# FuseReset_0_1.net
KiCad netlist of a schematic drawn in EAGLE
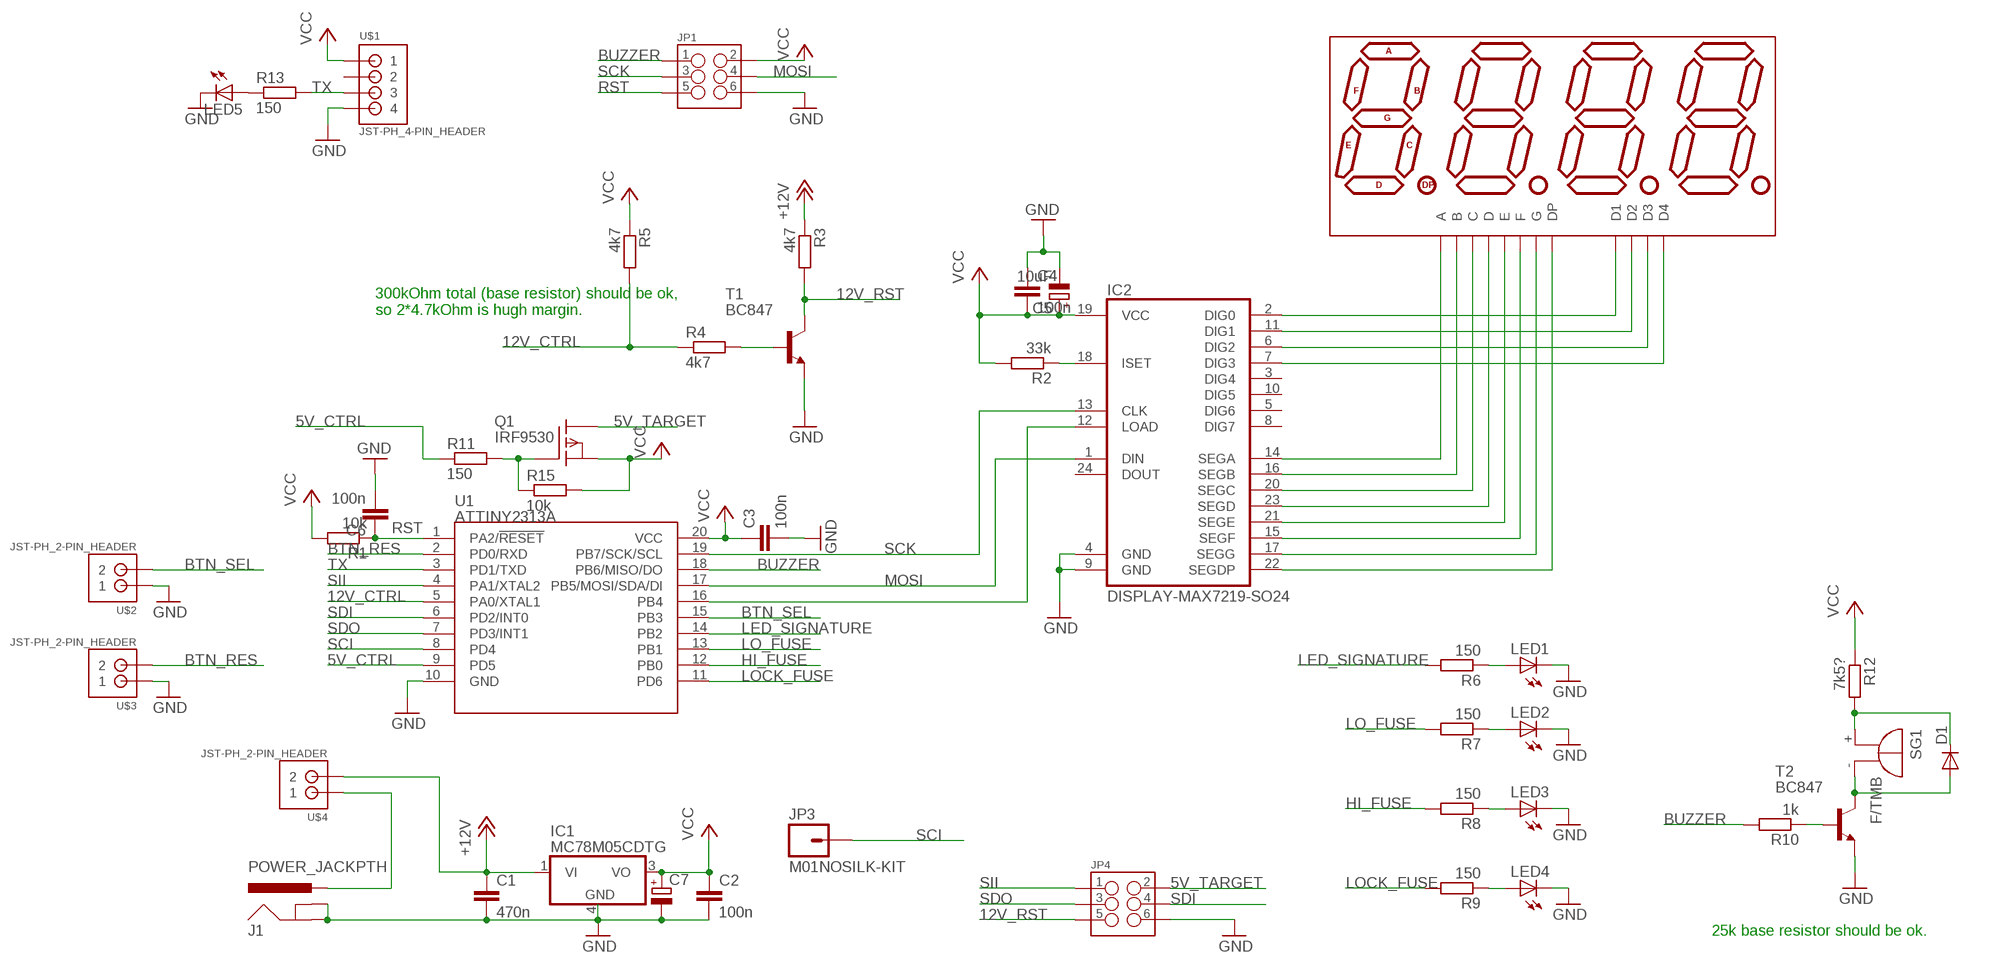
[diagram p0: schematic, sheet 1]

(export (version "E")
  (design (tool "Eeschema 10.0.6"))
  (components
    (comp (ref "C1")
      (value "470n")
      (footprint "eagle-import:C0805")
      (libsource (lib "eagle-import") (part "C-EUC0805"))
    )
    (comp (ref "C2")
      (value "100n")
      (footprint "eagle-import:C0805")
      (libsource (lib "eagle-import") (part "C-EUC0805"))
    )
    (comp (ref "C3")
      (value "100n")
      (footprint "eagle-import:C0805")
      (libsource (lib "eagle-import") (part "C-EUC0805"))
    )
    (comp (ref "C4")
      (value "100n")
      (footprint "eagle-import:C0805")
      (libsource (lib "eagle-import") (part "C-EUC0805"))
    )
    (comp (ref "C5")
      (value "10uF")
      (footprint "eagle-import:153CLV-0405")
      (libsource (lib "eagle-import") (part "resistor_CPOL-EU153CLV-0405"))
    )
    (comp (ref "C6")
      (value "100n")
      (footprint "eagle-import:C0805")
      (libsource (lib "eagle-import") (part "C-EUC0805"))
    )
    (comp (ref "C7")
      (value "CPOL-EUE2-5")
      (footprint "eagle-import:E2-5")
      (libsource (lib "eagle-import") (part "CPOL-EUE2-5"))
    )
    (comp (ref "D1")
      (value "DIODE-DO-214AC")
      (footprint "eagle-import:DO-214AC")
      (libsource (lib "eagle-import") (part "DIODE-DO-214AC"))
    )
    (comp (ref "DISP2")
      (value "7-SEGMENT-4DIGIT-COUNTER")
      (footprint "eagle-import:7-SEGMENT-4DIGIT-COUNTER-0.36_")
      (libsource (lib "eagle-import") (part "7-SEGMENT-4DIGIT-COUNTER"))
    )
    (comp (ref "IC1")
      (value "MC78M05CDTG")
      (footprint "eagle-import:DPACK_3")
      (libsource (lib "eagle-import") (part "MC78M05CDTG"))
    )
    (comp (ref "IC2")
      (value "DISPLAY-MAX7219-SO24")
      (footprint "eagle-import:SO24L")
      (libsource (lib "eagle-import") (part "DISPLAY-MAX7219-SO24"))
    )
    (comp (ref "J1")
      (value "POWER_JACKPTH")
      (footprint "eagle-import:POWER_JACK_PTH")
      (libsource (lib "eagle-import") (part "POWER_JACKPTH"))
    )
    (comp (ref "JP1")
      (value "M03X2SHROUD")
      (footprint "eagle-import:2X3-SHROUDED")
      (libsource (lib "eagle-import") (part "M03X2SHROUD"))
    )
    (comp (ref "JP3")
      (value "M01NOSILK-KIT")
      (footprint "eagle-import:1X01NS-KIT")
      (libsource (lib "eagle-import") (part "M01NOSILK-KIT"))
    )
    (comp (ref "JP4")
      (value "M03X2SHROUD")
      (footprint "eagle-import:2X3-SHROUDED")
      (libsource (lib "eagle-import") (part "M03X2SHROUD"))
    )
    (comp (ref "LED1")
      (value "LED3MM")
      (footprint "eagle-import:LED3MM")
      (libsource (lib "eagle-import") (part "LED3MM"))
    )
    (comp (ref "LED2")
      (value "LED3MM")
      (footprint "eagle-import:LED3MM")
      (libsource (lib "eagle-import") (part "LED3MM"))
    )
    (comp (ref "LED3")
      (value "LED3MM")
      (footprint "eagle-import:LED3MM")
      (libsource (lib "eagle-import") (part "LED3MM"))
    )
    (comp (ref "LED4")
      (value "LED3MM")
      (footprint "eagle-import:LED3MM")
      (libsource (lib "eagle-import") (part "LED3MM"))
    )
    (comp (ref "LED5")
      (value "LED-0805")
      (footprint "eagle-import:LED-805")
      (libsource (lib "eagle-import") (part "LED-0805"))
    )
    (comp (ref "Q1")
      (value "IRF9530")
      (footprint "eagle-import:TO220")
      (libsource (lib "eagle-import") (part "IRF9530"))
    )
    (comp (ref "R1")
      (value "10k")
      (footprint "eagle-import:R0805")
      (libsource (lib "eagle-import") (part "R-EU_R0805"))
    )
    (comp (ref "R2")
      (value "33k")
      (footprint "eagle-import:R0805")
      (libsource (lib "eagle-import") (part "R-EU_R0805"))
    )
    (comp (ref "R3")
      (value "4k7")
      (footprint "eagle-import:R0805")
      (libsource (lib "eagle-import") (part "R-EU_R0805"))
    )
    (comp (ref "R4")
      (value "4k7")
      (footprint "eagle-import:R0805")
      (libsource (lib "eagle-import") (part "R-EU_R0805"))
    )
    (comp (ref "R5")
      (value "4k7")
      (footprint "eagle-import:R0805")
      (libsource (lib "eagle-import") (part "R-EU_R0805"))
    )
    (comp (ref "R6")
      (value "150")
      (footprint "eagle-import:R0805")
      (libsource (lib "eagle-import") (part "R-EU_R0805"))
    )
    (comp (ref "R7")
      (value "150")
      (footprint "eagle-import:R0805")
      (libsource (lib "eagle-import") (part "R-EU_R0805"))
    )
    (comp (ref "R8")
      (value "150")
      (footprint "eagle-import:R0805")
      (libsource (lib "eagle-import") (part "R-EU_R0805"))
    )
    (comp (ref "R9")
      (value "150")
      (footprint "eagle-import:R0805")
      (libsource (lib "eagle-import") (part "R-EU_R0805"))
    )
    (comp (ref "R10")
      (value "1k")
      (footprint "eagle-import:R0805")
      (libsource (lib "eagle-import") (part "R-EU_R0805"))
    )
    (comp (ref "R11")
      (value "150")
      (footprint "eagle-import:R0805")
      (libsource (lib "eagle-import") (part "R-EU_R0805"))
    )
    (comp (ref "R12")
      (value "7k5?")
      (footprint "eagle-import:R0805")
      (libsource (lib "eagle-import") (part "R-EU_R0805"))
    )
    (comp (ref "R13")
      (value "150")
      (footprint "eagle-import:R0805")
      (libsource (lib "eagle-import") (part "R-EU_R0805"))
    )
    (comp (ref "R15")
      (value "10k")
      (footprint "eagle-import:R0805")
      (libsource (lib "eagle-import") (part "R-EU_R0805"))
    )
    (comp (ref "SG1")
      (value "F/TMB")
      (footprint "eagle-import:F_TMB")
      (libsource (lib "eagle-import") (part "F/TMB"))
    )
    (comp (ref "T1")
      (value "BC847")
      (footprint "eagle-import:SOT23")
      (libsource (lib "eagle-import") (part "BC847"))
    )
    (comp (ref "T2")
      (value "BC847")
      (footprint "eagle-import:SOT23")
      (libsource (lib "eagle-import") (part "BC847"))
    )
    (comp (ref "U$1")
      (value "JST-PH_4-PIN_HEADER")
      (footprint "eagle-import:JST_B4B-PH_HEADER")
      (libsource (lib "eagle-import") (part "JST-PH_4-PIN_HEADER"))
    )
    (comp (ref "U$2")
      (value "JST-PH_2-PIN_HEADER")
      (footprint "eagle-import:JST_B2B-PH_HEADER")
      (libsource (lib "eagle-import") (part "JST-PH_2-PIN_HEADER"))
    )
    (comp (ref "U$3")
      (value "JST-PH_2-PIN_HEADER")
      (footprint "eagle-import:JST_B2B-PH_HEADER")
      (libsource (lib "eagle-import") (part "JST-PH_2-PIN_HEADER"))
    )
    (comp (ref "U$4")
      (value "JST-PH_2-PIN_HEADER")
      (footprint "eagle-import:JST_B2B-PH_HEADER")
      (libsource (lib "eagle-import") (part "JST-PH_2-PIN_HEADER"))
    )
    (comp (ref "U1")
      (value "ATTINY2313A")
      (footprint "eagle-import:SOP20W")
      (libsource (lib "eagle-import") (part "ATTINY2313A"))
    )
  )
  (nets
    (net (code "1") (name "+12V") (class "Default")
      (node (ref "C1") (pin "1") (pinfunction "1_1") (pintype "passive"))
      (node (ref "IC1") (pin "1") (pinfunction "VI_1") (pintype "input"))
      (node (ref "R3") (pin "1") (pinfunction "1_1") (pintype "passive"))
      (node (ref "U$4") (pin "P2") (pinfunction "2_P2") (pintype "bidirectional"))
    )
    (net (code "2") (name "/5V_CTRL") (class "Default")
      (node (ref "R11") (pin "1") (pinfunction "1_1") (pintype "passive"))
      (node (ref "U1") (pin "9") (pinfunction "PD5_9") (pintype "bidirectional"))
    )
    (net (code "3") (name "/5V_TARGET") (class "Default")
      (node (ref "JP4") (pin "2") (pinfunction "2_2") (pintype "bidirectional"))
      (node (ref "Q1") (pin "2") (pinfunction "D_2") (pintype "passive"))
    )
    (net (code "4") (name "/12V_CTRL") (class "Default")
      (node (ref "R4") (pin "1") (pinfunction "1_1") (pintype "passive"))
      (node (ref "R5") (pin "2") (pinfunction "2_2") (pintype "passive"))
      (node (ref "U1") (pin "5") (pinfunction "PA0/XTAL1_5") (pintype "bidirectional"))
    )
    (net (code "5") (name "/12V_RST") (class "Default")
      (node (ref "JP4") (pin "5") (pinfunction "5_5") (pintype "bidirectional"))
      (node (ref "R3") (pin "2") (pinfunction "2_2") (pintype "passive"))
      (node (ref "T1") (pin "3") (pinfunction "C_3") (pintype "passive"))
    )
    (net (code "6") (name "/BTN_RES") (class "Default")
      (node (ref "U$3") (pin "P2") (pinfunction "2_P2") (pintype "bidirectional"))
      (node (ref "U1") (pin "2") (pinfunction "PD0/RXD_2") (pintype "bidirectional"))
    )
    (net (code "7") (name "/BTN_SEL") (class "Default")
      (node (ref "U$2") (pin "P2") (pinfunction "2_P2") (pintype "bidirectional"))
      (node (ref "U1") (pin "15") (pinfunction "PB3_15") (pintype "bidirectional"))
    )
    (net (code "8") (name "/BUZZER") (class "Default")
      (node (ref "JP1") (pin "1") (pinfunction "1_1") (pintype "bidirectional"))
      (node (ref "R10") (pin "2") (pinfunction "2_2") (pintype "passive"))
      (node (ref "U1") (pin "18") (pinfunction "PB6/MISO/DO_18") (pintype "bidirectional"))
    )
    (net (code "9") (name "/HI_FUSE") (class "Default")
      (node (ref "R8") (pin "2") (pinfunction "2_2") (pintype "passive"))
      (node (ref "U1") (pin "12") (pinfunction "PB0_12") (pintype "bidirectional"))
    )
    (net (code "10") (name "/LED_SIGNATURE") (class "Default")
      (node (ref "R6") (pin "2") (pinfunction "2_2") (pintype "passive"))
      (node (ref "U1") (pin "14") (pinfunction "PB2_14") (pintype "bidirectional"))
    )
    (net (code "11") (name "/LOCK_FUSE") (class "Default")
      (node (ref "R9") (pin "2") (pinfunction "2_2") (pintype "passive"))
      (node (ref "U1") (pin "11") (pinfunction "PD6_11") (pintype "bidirectional"))
    )
    (net (code "12") (name "/LO_FUSE") (class "Default")
      (node (ref "R7") (pin "2") (pinfunction "2_2") (pintype "passive"))
      (node (ref "U1") (pin "13") (pinfunction "PB1_13") (pintype "bidirectional"))
    )
    (net (code "13") (name "/MOSI") (class "Default")
      (node (ref "IC2") (pin "1") (pinfunction "DIN_1") (pintype "input"))
      (node (ref "JP1") (pin "4") (pinfunction "4_4") (pintype "bidirectional"))
      (node (ref "U1") (pin "17") (pinfunction "PB5/MOSI/SDA/DI_17") (pintype "bidirectional"))
    )
    (net (code "14") (name "/RST") (class "Default")
      (node (ref "C6") (pin "1") (pinfunction "1_1") (pintype "passive"))
      (node (ref "JP1") (pin "5") (pinfunction "5_5") (pintype "bidirectional"))
      (node (ref "R1") (pin "1") (pinfunction "1_1") (pintype "passive"))
      (node (ref "U1") (pin "1") (pinfunction "PA2/~{RESET}_1") (pintype "bidirectional"))
    )
    (net (code "15") (name "/SCI") (class "Default")
      (node (ref "JP3") (pin "1") (pinfunction "1_1") (pintype "passive"))
      (node (ref "U1") (pin "8") (pinfunction "PD4_8") (pintype "bidirectional"))
    )
    (net (code "16") (name "/SCK") (class "Default")
      (node (ref "IC2") (pin "13") (pinfunction "CLK_13") (pintype "input"))
      (node (ref "JP1") (pin "3") (pinfunction "3_3") (pintype "bidirectional"))
      (node (ref "U1") (pin "19") (pinfunction "PB7/SCK/SCL_19") (pintype "bidirectional"))
    )
    (net (code "17") (name "/SDI") (class "Default")
      (node (ref "JP4") (pin "4") (pinfunction "4_4") (pintype "bidirectional"))
      (node (ref "U1") (pin "6") (pinfunction "PD2/INT0_6") (pintype "bidirectional"))
    )
    (net (code "18") (name "/SDO") (class "Default")
      (node (ref "JP4") (pin "3") (pinfunction "3_3") (pintype "bidirectional"))
      (node (ref "U1") (pin "7") (pinfunction "PD3/INT1_7") (pintype "bidirectional"))
    )
    (net (code "19") (name "/SII") (class "Default")
      (node (ref "JP4") (pin "1") (pinfunction "1_1") (pintype "bidirectional"))
      (node (ref "U1") (pin "4") (pinfunction "PA1/XTAL2_4") (pintype "bidirectional"))
    )
    (net (code "20") (name "/TX") (class "Default")
      (node (ref "R13") (pin "2") (pinfunction "2_2") (pintype "passive"))
      (node (ref "U$1") (pin "P3") (pinfunction "3_P3") (pintype "bidirectional"))
      (node (ref "U1") (pin "3") (pinfunction "PD1/TXD_3") (pintype "bidirectional"))
    )
    (net (code "21") (name "GND") (class "Default")
      (node (ref "C1") (pin "2") (pinfunction "2_2") (pintype "passive"))
      (node (ref "C2") (pin "2") (pinfunction "2_2") (pintype "passive"))
      (node (ref "C3") (pin "2") (pinfunction "2_2") (pintype "passive"))
      (node (ref "C4") (pin "1") (pinfunction "1_1") (pintype "passive"))
      (node (ref "C5") (pin "-") (pinfunction "-_-") (pintype "passive"))
      (node (ref "C6") (pin "2") (pinfunction "2_2") (pintype "passive"))
      (node (ref "C7") (pin "-") (pinfunction "-_-") (pintype "passive"))
      (node (ref "IC1") (pin "4") (pinfunction "GND_4") (pintype "passive"))
      (node (ref "IC2") (pin "4") (pinfunction "GND_4") (pintype "power_in"))
      (node (ref "IC2") (pin "9") (pinfunction "GND_9") (pintype "power_in"))
      (node (ref "J1") (pin "GND") (pinfunction "GND_GND") (pintype "bidirectional"))
      (node (ref "J1") (pin "GNDBREAK") (pinfunction "GNDBREAK_GNDBREAK") (pintype "bidirectional"))
      (node (ref "JP1") (pin "6") (pinfunction "6_6") (pintype "bidirectional"))
      (node (ref "JP4") (pin "6") (pinfunction "6_6") (pintype "bidirectional"))
      (node (ref "LED1") (pin "K") (pinfunction "C_K") (pintype "passive"))
      (node (ref "LED2") (pin "K") (pinfunction "C_K") (pintype "passive"))
      (node (ref "LED3") (pin "K") (pinfunction "C_K") (pintype "passive"))
      (node (ref "LED4") (pin "K") (pinfunction "C_K") (pintype "passive"))
      (node (ref "LED5") (pin "C") (pinfunction "C_C") (pintype "passive"))
      (node (ref "T1") (pin "2") (pinfunction "E_2") (pintype "passive"))
      (node (ref "T2") (pin "2") (pinfunction "E_2") (pintype "passive"))
      (node (ref "U$1") (pin "P4") (pinfunction "4_P4") (pintype "bidirectional"))
      (node (ref "U$2") (pin "P1") (pinfunction "1_P1") (pintype "bidirectional"))
      (node (ref "U$3") (pin "P1") (pinfunction "1_P1") (pintype "bidirectional"))
      (node (ref "U1") (pin "10") (pinfunction "GND_10") (pintype "bidirectional"))
    )
    (net (code "22") (name "Net-(D1-A)") (class "Default")
      (node (ref "D1") (pin "2") (pinfunction "A_2") (pintype "passive"))
      (node (ref "SG1") (pin "-") (pinfunction "-_-") (pintype "passive"))
      (node (ref "T2") (pin "3") (pinfunction "C_3") (pintype "passive"))
    )
    (net (code "23") (name "Net-(D1-C)") (class "Default")
      (node (ref "D1") (pin "1") (pinfunction "C_1") (pintype "passive"))
      (node (ref "R12") (pin "2") (pinfunction "2_2") (pintype "passive"))
      (node (ref "SG1") (pin "+") (pinfunction "+_+") (pintype "passive"))
    )
    (net (code "24") (name "Net-(DISP2-A)") (class "Default")
      (node (ref "DISP2") (pin "11") (pinfunction "A_11") (pintype "bidirectional"))
      (node (ref "IC2") (pin "14") (pinfunction "SEGA_14") (pintype "output"))
    )
    (net (code "25") (name "Net-(DISP2-B)") (class "Default")
      (node (ref "DISP2") (pin "7") (pinfunction "B_7") (pintype "bidirectional"))
      (node (ref "IC2") (pin "16") (pinfunction "SEGB_16") (pintype "output"))
    )
    (net (code "26") (name "Net-(DISP2-C)") (class "Default")
      (node (ref "DISP2") (pin "4") (pinfunction "C_4") (pintype "bidirectional"))
      (node (ref "IC2") (pin "20") (pinfunction "SEGC_20") (pintype "output"))
    )
    (net (code "27") (name "Net-(DISP2-D)") (class "Default")
      (node (ref "DISP2") (pin "2") (pinfunction "D_2") (pintype "bidirectional"))
      (node (ref "IC2") (pin "23") (pinfunction "SEGD_23") (pintype "output"))
    )
    (net (code "28") (name "Net-(DISP2-D1)") (class "Default")
      (node (ref "DISP2") (pin "12") (pinfunction "D1_12") (pintype "bidirectional"))
      (node (ref "IC2") (pin "2") (pinfunction "DIG0_2") (pintype "output"))
    )
    (net (code "29") (name "Net-(DISP2-D2)") (class "Default")
      (node (ref "DISP2") (pin "9") (pinfunction "D2_9") (pintype "bidirectional"))
      (node (ref "IC2") (pin "11") (pinfunction "DIG1_11") (pintype "output"))
    )
    (net (code "30") (name "Net-(DISP2-D3)") (class "Default")
      (node (ref "DISP2") (pin "8") (pinfunction "D3_8") (pintype "bidirectional"))
      (node (ref "IC2") (pin "6") (pinfunction "DIG2_6") (pintype "output"))
    )
    (net (code "31") (name "Net-(DISP2-D4)") (class "Default")
      (node (ref "DISP2") (pin "6") (pinfunction "D4_6") (pintype "bidirectional"))
      (node (ref "IC2") (pin "7") (pinfunction "DIG3_7") (pintype "output"))
    )
    (net (code "32") (name "Net-(DISP2-DP)") (class "Default")
      (node (ref "DISP2") (pin "3") (pinfunction "DP_3") (pintype "bidirectional"))
      (node (ref "IC2") (pin "22") (pinfunction "SEGDP_22") (pintype "output"))
    )
    (net (code "33") (name "Net-(DISP2-E)") (class "Default")
      (node (ref "DISP2") (pin "1") (pinfunction "E_1") (pintype "bidirectional"))
      (node (ref "IC2") (pin "21") (pinfunction "SEGE_21") (pintype "output"))
    )
    (net (code "34") (name "Net-(DISP2-F)") (class "Default")
      (node (ref "DISP2") (pin "10") (pinfunction "F_10") (pintype "bidirectional"))
      (node (ref "IC2") (pin "15") (pinfunction "SEGF_15") (pintype "output"))
    )
    (net (code "35") (name "Net-(DISP2-G)") (class "Default")
      (node (ref "DISP2") (pin "5") (pinfunction "G_5") (pintype "bidirectional"))
      (node (ref "IC2") (pin "17") (pinfunction "SEGG_17") (pintype "output"))
    )
    (net (code "36") (name "Net-(IC2-ISET)") (class "Default")
      (node (ref "IC2") (pin "18") (pinfunction "ISET_18") (pintype "input"))
      (node (ref "R2") (pin "1") (pinfunction "1_1") (pintype "passive"))
    )
    (net (code "37") (name "Net-(IC2-LOAD)") (class "Default")
      (node (ref "IC2") (pin "12") (pinfunction "LOAD_12") (pintype "input"))
      (node (ref "U1") (pin "16") (pinfunction "PB4_16") (pintype "bidirectional"))
    )
    (net (code "38") (name "Net-(LED1-PadA)") (class "Default")
      (node (ref "LED1") (pin "A") (pinfunction "A_A") (pintype "passive"))
      (node (ref "R6") (pin "1") (pinfunction "1_1") (pintype "passive"))
    )
    (net (code "39") (name "Net-(LED2-PadA)") (class "Default")
      (node (ref "LED2") (pin "A") (pinfunction "A_A") (pintype "passive"))
      (node (ref "R7") (pin "1") (pinfunction "1_1") (pintype "passive"))
    )
    (net (code "40") (name "Net-(LED3-PadA)") (class "Default")
      (node (ref "LED3") (pin "A") (pinfunction "A_A") (pintype "passive"))
      (node (ref "R8") (pin "1") (pinfunction "1_1") (pintype "passive"))
    )
    (net (code "41") (name "Net-(LED4-PadA)") (class "Default")
      (node (ref "LED4") (pin "A") (pinfunction "A_A") (pintype "passive"))
      (node (ref "R9") (pin "1") (pinfunction "1_1") (pintype "passive"))
    )
    (net (code "42") (name "Net-(LED5-PadA)") (class "Default")
      (node (ref "LED5") (pin "A") (pinfunction "A_A") (pintype "passive"))
      (node (ref "R13") (pin "1") (pinfunction "1_1") (pintype "passive"))
    )
    (net (code "43") (name "Net-(Q1-G)") (class "Default")
      (node (ref "Q1") (pin "1") (pinfunction "G_1") (pintype "passive"))
      (node (ref "R11") (pin "2") (pinfunction "2_2") (pintype "passive"))
      (node (ref "R15") (pin "1") (pinfunction "1_1") (pintype "passive"))
    )
    (net (code "44") (name "Net-(T1-B)") (class "Default")
      (node (ref "R4") (pin "2") (pinfunction "2_2") (pintype "passive"))
      (node (ref "T1") (pin "1") (pinfunction "B_1") (pintype "passive"))
    )
    (net (code "45") (name "Net-(T2-B)") (class "Default")
      (node (ref "R10") (pin "1") (pinfunction "1_1") (pintype "passive"))
      (node (ref "T2") (pin "1") (pinfunction "B_1") (pintype "passive"))
    )
    (net (code "46") (name "Net-(U$4-1)") (class "Default")
      (node (ref "J1") (pin "PWR") (pinfunction "PWR_PWR") (pintype "bidirectional"))
      (node (ref "U$4") (pin "P1") (pinfunction "1_P1") (pintype "bidirectional"))
    )
    (net (code "47") (name "VCC") (class "Default")
      (node (ref "C2") (pin "1") (pinfunction "1_1") (pintype "passive"))
      (node (ref "C3") (pin "1") (pinfunction "1_1") (pintype "passive"))
      (node (ref "C4") (pin "2") (pinfunction "2_2") (pintype "passive"))
      (node (ref "C5") (pin "+") (pinfunction "+_+") (pintype "passive"))
      (node (ref "C7") (pin "+") (pinfunction "+_+") (pintype "passive"))
      (node (ref "IC1") (pin "3") (pinfunction "VO_3") (pintype "passive"))
      (node (ref "IC2") (pin "19") (pinfunction "VCC_19") (pintype "power_in"))
      (node (ref "JP1") (pin "2") (pinfunction "2_2") (pintype "bidirectional"))
      (node (ref "Q1") (pin "3") (pinfunction "S_3") (pintype "passive"))
      (node (ref "R1") (pin "2") (pinfunction "2_2") (pintype "passive"))
      (node (ref "R12") (pin "1") (pinfunction "1_1") (pintype "passive"))
      (node (ref "R15") (pin "2") (pinfunction "2_2") (pintype "passive"))
      (node (ref "R2") (pin "2") (pinfunction "2_2") (pintype "passive"))
      (node (ref "R5") (pin "1") (pinfunction "1_1") (pintype "passive"))
      (node (ref "U$1") (pin "P1") (pinfunction "1_P1") (pintype "bidirectional"))
      (node (ref "U1") (pin "20") (pinfunction "VCC_20") (pintype "bidirectional"))
    )
    (net (code "48") (name "unconnected-(IC2-DIG4-Pad3)") (class "Default")
      (node (ref "IC2") (pin "3") (pinfunction "DIG4_3") (pintype "output"))
    )
    (net (code "49") (name "unconnected-(IC2-DIG5-Pad10)") (class "Default")
      (node (ref "IC2") (pin "10") (pinfunction "DIG5_10") (pintype "output"))
    )
    (net (code "50") (name "unconnected-(IC2-DIG6-Pad5)") (class "Default")
      (node (ref "IC2") (pin "5") (pinfunction "DIG6_5") (pintype "output"))
    )
    (net (code "51") (name "unconnected-(IC2-DIG7-Pad8)") (class "Default")
      (node (ref "IC2") (pin "8") (pinfunction "DIG7_8") (pintype "output"))
    )
    (net (code "52") (name "unconnected-(IC2-DOUT-Pad24)") (class "Default")
      (node (ref "IC2") (pin "24") (pinfunction "DOUT_24") (pintype "output"))
    )
    (net (code "53") (name "unconnected-(U$1-2-PadP2)") (class "Default")
      (node (ref "U$1") (pin "P2") (pinfunction "2_P2") (pintype "bidirectional"))
    )
  )
)
